# MiniDuino.net
KiCad netlist of a schematic drawn in EAGLE
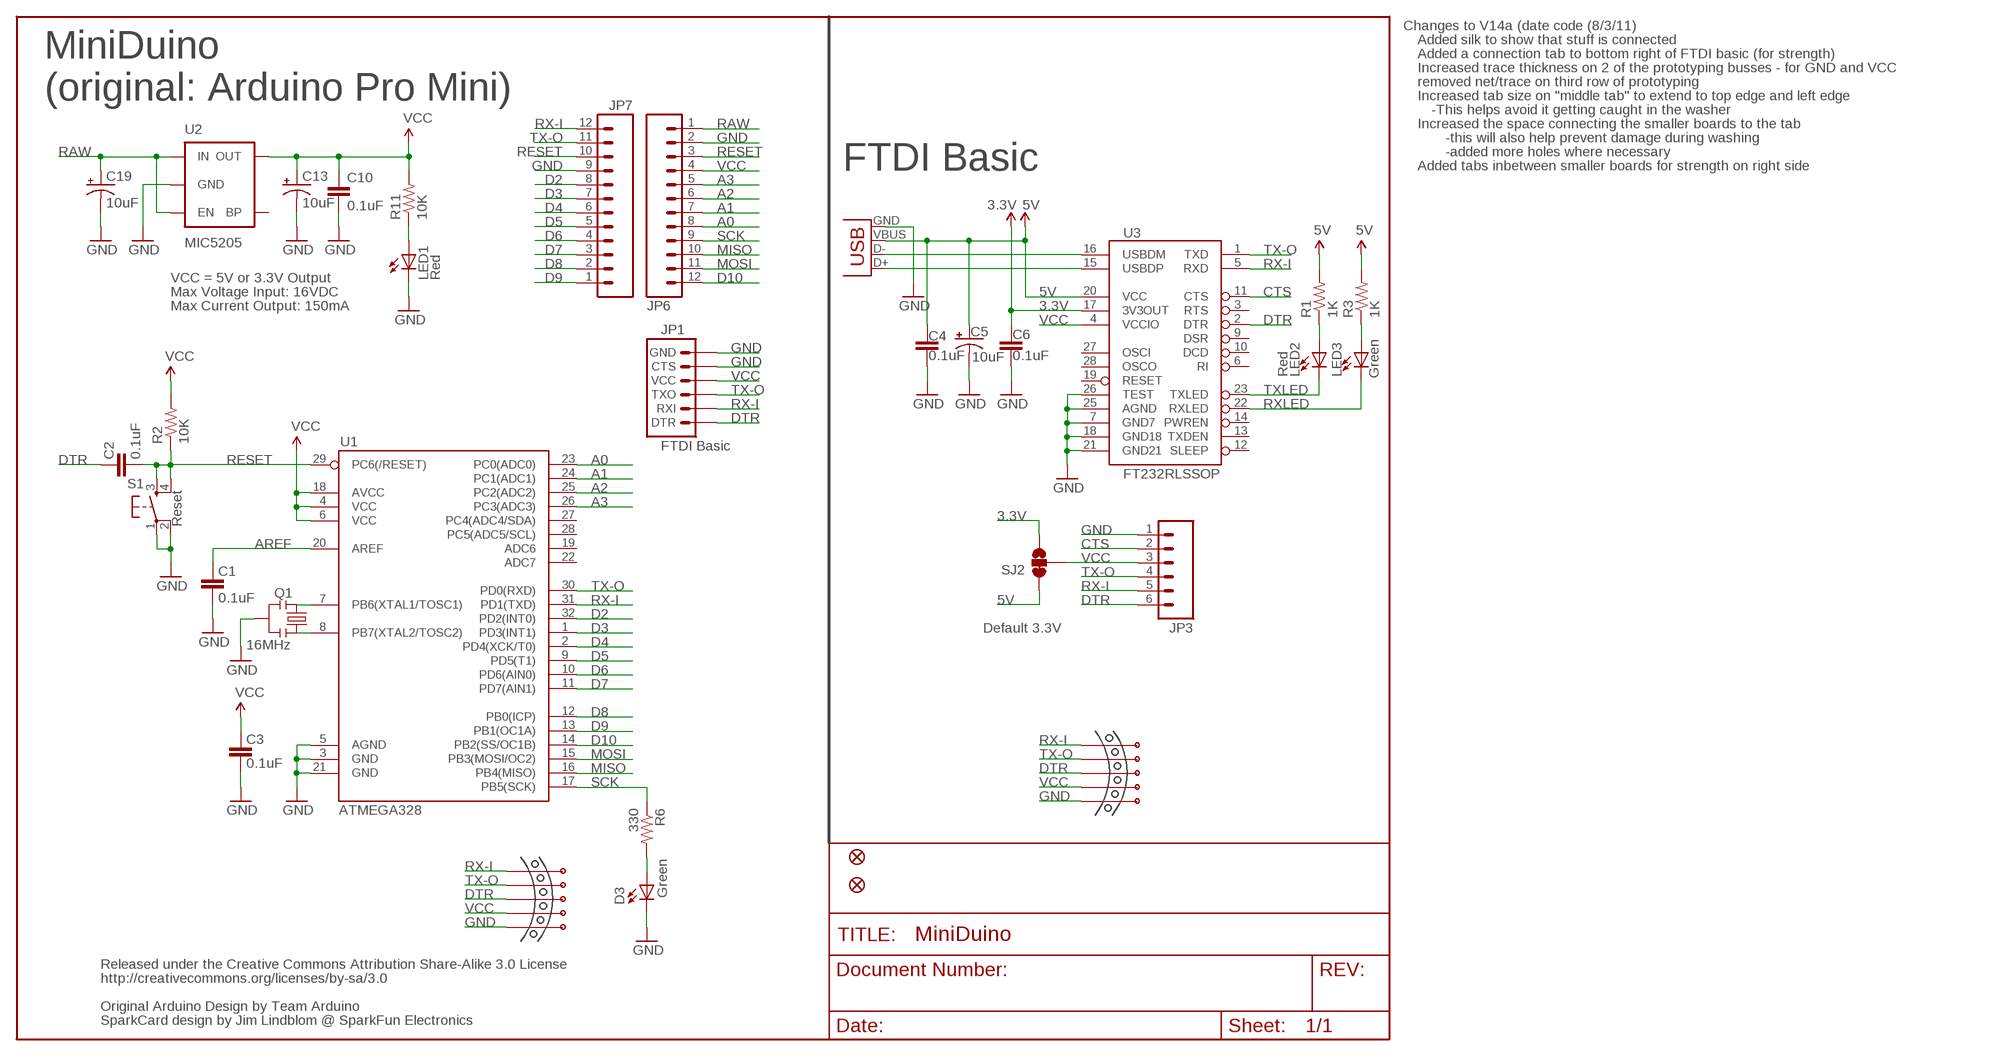
[diagram p0: schematic, sheet 1]

(export (version "E")
  (design (tool "Eeschema 10.0.6"))
  (components
    (comp (ref "C1")
      (value "0.1uF")
      (footprint "eagle-import:0402-CAP")
      (libsource (lib "eagle-import") (part "CAP0402-CAP"))
    )
    (comp (ref "C2")
      (value "0.1uF")
      (footprint "eagle-import:0402-CAP")
      (libsource (lib "eagle-import") (part "CAP0402-CAP"))
    )
    (comp (ref "C3")
      (value "0.1uF")
      (footprint "eagle-import:0402-CAP")
      (libsource (lib "eagle-import") (part "CAP0402-CAP"))
    )
    (comp (ref "C4")
      (value "0.1uF")
      (footprint "eagle-import:0402-CAP")
      (libsource (lib "eagle-import") (part "CAP0402-CAP"))
    )
    (comp (ref "C5")
      (value "10uF")
      (footprint "eagle-import:EIA3216")
      (libsource (lib "eagle-import") (part "CAP_POL1206"))
    )
    (comp (ref "C6")
      (value "0.1uF")
      (footprint "eagle-import:0402-CAP")
      (libsource (lib "eagle-import") (part "CAP0402-CAP"))
    )
    (comp (ref "C10")
      (value "0.1uF")
      (footprint "eagle-import:0402-CAP")
      (libsource (lib "eagle-import") (part "CAP0402-CAP"))
    )
    (comp (ref "C13")
      (value "10uF")
      (footprint "eagle-import:EIA3216")
      (libsource (lib "eagle-import") (part "CAP_POL1206"))
    )
    (comp (ref "C19")
      (value "10uF")
      (footprint "eagle-import:EIA3216")
      (libsource (lib "eagle-import") (part "CAP_POL1206"))
    )
    (comp (ref "D3")
      (value "Green")
      (footprint "eagle-import:LED-0603")
      (libsource (lib "eagle-import") (part "LED0603"))
    )
    (comp (ref "JP1")
      (value "FTDI Basic")
      (footprint "eagle-import:1X06")
      (libsource (lib "eagle-import") (part "ARDUINO_SERIAL_PROGRAMPTH"))
    )
    (comp (ref "JP3")
      (value "M06SIP")
      (footprint "eagle-import:1X06")
      (libsource (lib "eagle-import") (part "M06SIP"))
    )
    (comp (ref "JP6")
      (value "M12PTH")
      (footprint "eagle-import:1X12")
      (libsource (lib "eagle-import") (part "M12PTH"))
    )
    (comp (ref "JP7")
      (value "M12PTH")
      (footprint "eagle-import:1X12")
      (libsource (lib "eagle-import") (part "M12PTH"))
    )
    (comp (ref "JP16")
      (value "FIDUCIAL1X2.5")
      (footprint "eagle-import:FIDUCIAL-1X2.5")
      (libsource (lib "eagle-import") (part "FIDUCIAL1X2.5"))
    )
    (comp (ref "JP19")
      (value "FIDUCIAL1X2.5")
      (footprint "eagle-import:FIDUCIAL-1X2.5")
      (libsource (lib "eagle-import") (part "FIDUCIAL1X2.5"))
    )
    (comp (ref "LED1")
      (value "Red")
      (footprint "eagle-import:LED-0603")
      (libsource (lib "eagle-import") (part "LED0603"))
    )
    (comp (ref "LED2")
      (value "Red")
      (footprint "eagle-import:LED-0603")
      (libsource (lib "eagle-import") (part "LED0603"))
    )
    (comp (ref "LED3")
      (value "Green")
      (footprint "eagle-import:LED-0603")
      (libsource (lib "eagle-import") (part "LED0603"))
    )
    (comp (ref "Q1")
      (value "16MHz")
      (footprint "eagle-import:RESONATOR-SMD")
      (libsource (lib "eagle-import") (part "RESONATORSMD"))
    )
    (comp (ref "R1")
      (value "1K")
      (footprint "eagle-import:0402-RES")
      (libsource (lib "eagle-import") (part "RESISTOR0402-RES"))
    )
    (comp (ref "R2")
      (value "10K")
      (footprint "eagle-import:0402-RES")
      (libsource (lib "eagle-import") (part "RESISTOR0402-RES"))
    )
    (comp (ref "R3")
      (value "1K")
      (footprint "eagle-import:0402-RES")
      (libsource (lib "eagle-import") (part "RESISTOR0402-RES"))
    )
    (comp (ref "R6")
      (value "330")
      (footprint "eagle-import:0402-RES")
      (libsource (lib "eagle-import") (part "RESISTOR0402-RES"))
    )
    (comp (ref "R11")
      (value "10K")
      (footprint "eagle-import:0402-RES")
      (libsource (lib "eagle-import") (part "RESISTOR0402-RES"))
    )
    (comp (ref "S1")
      (value "Reset")
      (footprint "eagle-import:TACTILE_SWITCH_SMD")
      (libsource (lib "eagle-import") (part "TAC_SWITCHSMD"))
    )
    (comp (ref "SJ2")
      (value "SOLDERJUMPER_2WAYS")
      (footprint "eagle-import:SJ_3")
      (libsource (lib "eagle-import") (part "SOLDERJUMPER_2WAYS"))
    )
    (comp (ref "U$22")
      (value "MOUSE-BITE-5")
      (footprint "eagle-import:MOUSE-BITE-5")
      (libsource (lib "eagle-import") (part "MOUSE-BITE-5"))
    )
    (comp (ref "U$23")
      (value "MOUSE-BITE-5")
      (footprint "eagle-import:MOUSE-BITE-5")
      (libsource (lib "eagle-import") (part "MOUSE-BITE-5"))
    )
    (comp (ref "U1")
      (value "ATMEGA328")
      (footprint "eagle-import:TQFP32-08")
      (libsource (lib "eagle-import") (part "ATMEGA168"))
    )
    (comp (ref "U2")
      (value "MIC5205")
      (footprint "eagle-import:SOT23-5")
      (libsource (lib "eagle-import") (part "V_REG_LDOSMD"))
    )
    (comp (ref "U3")
      (value "FT232RLSSOP")
      (footprint "eagle-import:SSOP28DB")
      (libsource (lib "eagle-import") (part "FT232RLSSOP"))
    )
    (comp (ref "X2")
      (value "USB-SMD-NS")
      (footprint "eagle-import:USB-MINIB-NOSTOP")
      (libsource (lib "eagle-import") (part "USB-SMD-NS"))
    )
  )
  (nets
    (net (code "1") (name "/A0") (class "Default")
      (node (ref "JP6") (pin "8") (pinfunction "8_8") (pintype "passive"))
      (node (ref "U1") (pin "23") (pinfunction "PC0(ADC0)_23") (pintype "bidirectional"))
    )
    (net (code "2") (name "/A1") (class "Default")
      (node (ref "JP6") (pin "7") (pinfunction "7_7") (pintype "passive"))
      (node (ref "U1") (pin "24") (pinfunction "PC1(ADC1)_24") (pintype "bidirectional"))
    )
    (net (code "3") (name "/A2") (class "Default")
      (node (ref "JP6") (pin "6") (pinfunction "6_6") (pintype "passive"))
      (node (ref "U1") (pin "25") (pinfunction "PC2(ADC2)_25") (pintype "bidirectional"))
    )
    (net (code "4") (name "/A3") (class "Default")
      (node (ref "JP6") (pin "5") (pinfunction "5_5") (pintype "passive"))
      (node (ref "U1") (pin "26") (pinfunction "PC3(ADC3)_26") (pintype "bidirectional"))
    )
    (net (code "5") (name "/AREF") (class "Default")
      (node (ref "C1") (pin "2") (pinfunction "2_2") (pintype "passive"))
      (node (ref "U1") (pin "20") (pinfunction "AREF_20") (pintype "bidirectional"))
    )
    (net (code "6") (name "/CTS") (class "Default")
      (node (ref "JP3") (pin "2") (pinfunction "2_2") (pintype "passive"))
      (node (ref "U3") (pin "11") (pinfunction "CTS_11") (pintype "input"))
    )
    (net (code "7") (name "/D2") (class "Default")
      (node (ref "JP7") (pin "8") (pinfunction "8_8") (pintype "passive"))
      (node (ref "U1") (pin "32") (pinfunction "PD2(INT0)_32") (pintype "bidirectional"))
    )
    (net (code "8") (name "/D3") (class "Default")
      (node (ref "JP7") (pin "7") (pinfunction "7_7") (pintype "passive"))
      (node (ref "U1") (pin "1") (pinfunction "PD3(INT1)_1") (pintype "bidirectional"))
    )
    (net (code "9") (name "/D4") (class "Default")
      (node (ref "JP7") (pin "6") (pinfunction "6_6") (pintype "passive"))
      (node (ref "U1") (pin "2") (pinfunction "PD4(XCK/T0)_2") (pintype "bidirectional"))
    )
    (net (code "10") (name "/D5") (class "Default")
      (node (ref "JP7") (pin "5") (pinfunction "5_5") (pintype "passive"))
      (node (ref "U1") (pin "9") (pinfunction "PD5(T1)_9") (pintype "bidirectional"))
    )
    (net (code "11") (name "/D6") (class "Default")
      (node (ref "JP7") (pin "4") (pinfunction "4_4") (pintype "passive"))
      (node (ref "U1") (pin "10") (pinfunction "PD6(AIN0)_10") (pintype "bidirectional"))
    )
    (net (code "12") (name "/D7") (class "Default")
      (node (ref "JP7") (pin "3") (pinfunction "3_3") (pintype "passive"))
      (node (ref "U1") (pin "11") (pinfunction "PD7(AIN1)_11") (pintype "bidirectional"))
    )
    (net (code "13") (name "/D8") (class "Default")
      (node (ref "JP7") (pin "2") (pinfunction "2_2") (pintype "passive"))
      (node (ref "U1") (pin "12") (pinfunction "PB0(ICP)_12") (pintype "bidirectional"))
    )
    (net (code "14") (name "/D9") (class "Default")
      (node (ref "JP7") (pin "1") (pinfunction "1_1") (pintype "passive"))
      (node (ref "U1") (pin "13") (pinfunction "PB1(OC1A)_13") (pintype "bidirectional"))
    )
    (net (code "15") (name "/D10") (class "Default")
      (node (ref "JP6") (pin "12") (pinfunction "12_12") (pintype "passive"))
      (node (ref "U1") (pin "14") (pinfunction "PB2(SS/OC1B)_14") (pintype "bidirectional"))
    )
    (net (code "16") (name "/DTR") (class "Default")
      (node (ref "C2") (pin "2") (pinfunction "2_2") (pintype "passive"))
      (node (ref "JP1") (pin "1") (pinfunction "DTR_1") (pintype "passive"))
      (node (ref "JP3") (pin "6") (pinfunction "6_6") (pintype "passive"))
      (node (ref "U$22") (pin "P$3") (pinfunction "P$3_P$3") (pintype "bidirectional"))
      (node (ref "U$23") (pin "P$3") (pinfunction "P$3_P$3") (pintype "bidirectional"))
      (node (ref "U3") (pin "2") (pinfunction "DTR_2") (pintype "output"))
    )
    (net (code "17") (name "/MISO") (class "Default")
      (node (ref "JP6") (pin "10") (pinfunction "10_10") (pintype "passive"))
      (node (ref "U1") (pin "16") (pinfunction "PB4(MISO)_16") (pintype "bidirectional"))
    )
    (net (code "18") (name "/MOSI") (class "Default")
      (node (ref "JP6") (pin "11") (pinfunction "11_11") (pintype "passive"))
      (node (ref "U1") (pin "15") (pinfunction "PB3(MOSI/OC2)_15") (pintype "bidirectional"))
    )
    (net (code "19") (name "/RAW") (class "Default")
      (node (ref "C19") (pin "A") (pinfunction "+_A") (pintype "passive"))
      (node (ref "JP6") (pin "1") (pinfunction "1_1") (pintype "passive"))
      (node (ref "U2") (pin "1") (pinfunction "IN_1") (pintype "input"))
      (node (ref "U2") (pin "3") (pinfunction "EN_3") (pintype "input"))
    )
    (net (code "20") (name "/RESET") (class "Default")
      (node (ref "C2") (pin "1") (pinfunction "1_1") (pintype "passive"))
      (node (ref "JP6") (pin "3") (pinfunction "3_3") (pintype "passive"))
      (node (ref "JP7") (pin "10") (pinfunction "10_10") (pintype "passive"))
      (node (ref "R2") (pin "1") (pinfunction "1_1") (pintype "passive"))
      (node (ref "S1") (pin "3") (pinfunction "3_3") (pintype "passive"))
      (node (ref "S1") (pin "4") (pinfunction "4_4") (pintype "passive"))
      (node (ref "U1") (pin "29") (pinfunction "PC6(/RESET)_29") (pintype "bidirectional"))
    )
    (net (code "21") (name "/RX-I") (class "Default")
      (node (ref "JP1") (pin "2") (pinfunction "RXI_2") (pintype "passive"))
      (node (ref "JP3") (pin "5") (pinfunction "5_5") (pintype "passive"))
      (node (ref "JP7") (pin "12") (pinfunction "12_12") (pintype "passive"))
      (node (ref "U$22") (pin "P$1") (pinfunction "P$1_P$1") (pintype "bidirectional"))
      (node (ref "U$23") (pin "P$1") (pinfunction "P$1_P$1") (pintype "bidirectional"))
      (node (ref "U1") (pin "31") (pinfunction "PD1(TXD)_31") (pintype "bidirectional"))
      (node (ref "U3") (pin "5") (pinfunction "RXD_5") (pintype "input"))
    )
    (net (code "22") (name "/RXLED") (class "Default")
      (node (ref "LED3") (pin "C") (pinfunction "C_C") (pintype "passive"))
      (node (ref "U3") (pin "22") (pinfunction "RXLED_22") (pintype "input"))
    )
    (net (code "23") (name "/SCK") (class "Default")
      (node (ref "JP6") (pin "9") (pinfunction "9_9") (pintype "passive"))
      (node (ref "R6") (pin "1") (pinfunction "1_1") (pintype "passive"))
      (node (ref "U1") (pin "17") (pinfunction "PB5(SCK)_17") (pintype "bidirectional"))
    )
    (net (code "24") (name "/TX-O") (class "Default")
      (node (ref "JP1") (pin "3") (pinfunction "TXO_3") (pintype "passive"))
      (node (ref "JP3") (pin "4") (pinfunction "4_4") (pintype "passive"))
      (node (ref "JP7") (pin "11") (pinfunction "11_11") (pintype "passive"))
      (node (ref "U$22") (pin "P$2") (pinfunction "P$2_P$2") (pintype "bidirectional"))
      (node (ref "U$23") (pin "P$2") (pinfunction "P$2_P$2") (pintype "bidirectional"))
      (node (ref "U1") (pin "30") (pinfunction "PD0(RXD)_30") (pintype "bidirectional"))
      (node (ref "U3") (pin "1") (pinfunction "TXD_1") (pintype "output"))
    )
    (net (code "25") (name "/TXLED") (class "Default")
      (node (ref "LED2") (pin "C") (pinfunction "C_C") (pintype "passive"))
      (node (ref "U3") (pin "23") (pinfunction "TXLED_23") (pintype "input"))
    )
    (net (code "26") (name "3.3V") (class "Default")
      (node (ref "C6") (pin "1") (pinfunction "1_1") (pintype "passive"))
      (node (ref "SJ2") (pin "3") (pinfunction "3_3") (pintype "passive"))
      (node (ref "U3") (pin "17") (pinfunction "3V3OUT_17") (pintype "output"))
    )
    (net (code "27") (name "5V") (class "Default")
      (node (ref "C4") (pin "1") (pinfunction "1_1") (pintype "passive"))
      (node (ref "C5") (pin "A") (pinfunction "+_A") (pintype "passive"))
      (node (ref "R1") (pin "2") (pinfunction "2_2") (pintype "passive"))
      (node (ref "R3") (pin "2") (pinfunction "2_2") (pintype "passive"))
      (node (ref "SJ2") (pin "1") (pinfunction "1_1") (pintype "passive"))
      (node (ref "U3") (pin "20") (pinfunction "VCC_20") (pintype "power_in"))
      (node (ref "X2") (pin "VBUS") (pinfunction "VBUS_VBUS") (pintype "bidirectional"))
    )
    (net (code "28") (name "GND") (class "Default")
      (node (ref "C1") (pin "1") (pinfunction "1_1") (pintype "passive"))
      (node (ref "C10") (pin "2") (pinfunction "2_2") (pintype "passive"))
      (node (ref "C13") (pin "C") (pinfunction "-_C") (pintype "passive"))
      (node (ref "C19") (pin "C") (pinfunction "-_C") (pintype "passive"))
      (node (ref "C3") (pin "1") (pinfunction "1_1") (pintype "passive"))
      (node (ref "C4") (pin "2") (pinfunction "2_2") (pintype "passive"))
      (node (ref "C5") (pin "C") (pinfunction "-_C") (pintype "passive"))
      (node (ref "C6") (pin "2") (pinfunction "2_2") (pintype "passive"))
      (node (ref "D3") (pin "C") (pinfunction "C_C") (pintype "passive"))
      (node (ref "JP1") (pin "5") (pinfunction "CTS_5") (pintype "passive"))
      (node (ref "JP1") (pin "6") (pinfunction "GND_6") (pintype "passive"))
      (node (ref "JP3") (pin "1") (pinfunction "1_1") (pintype "passive"))
      (node (ref "JP6") (pin "2") (pinfunction "2_2") (pintype "passive"))
      (node (ref "JP7") (pin "9") (pinfunction "9_9") (pintype "passive"))
      (node (ref "LED1") (pin "C") (pinfunction "C_C") (pintype "passive"))
      (node (ref "Q1") (pin "2") (pinfunction "2_2") (pintype "passive"))
      (node (ref "S1") (pin "1") (pinfunction "1_1") (pintype "passive"))
      (node (ref "S1") (pin "2") (pinfunction "2_2") (pintype "passive"))
      (node (ref "U$22") (pin "P$5") (pinfunction "P$5_P$5") (pintype "bidirectional"))
      (node (ref "U$23") (pin "P$5") (pinfunction "P$5_P$5") (pintype "bidirectional"))
      (node (ref "U1") (pin "21") (pinfunction "GND_21") (pintype "bidirectional"))
      (node (ref "U1") (pin "3") (pinfunction "GND_3") (pintype "bidirectional"))
      (node (ref "U1") (pin "5") (pinfunction "AGND_5") (pintype "bidirectional"))
      (node (ref "U2") (pin "2") (pinfunction "GND_2") (pintype "input"))
      (node (ref "U3") (pin "18") (pinfunction "GND18_18") (pintype "power_in"))
      (node (ref "U3") (pin "21") (pinfunction "GND21_21") (pintype "power_in"))
      (node (ref "U3") (pin "25") (pinfunction "AGND_25") (pintype "power_in"))
      (node (ref "U3") (pin "26") (pinfunction "TEST_26") (pintype "input"))
      (node (ref "U3") (pin "7") (pinfunction "GND7_7") (pintype "power_in"))
      (node (ref "X2") (pin "GND") (pinfunction "GND_GND") (pintype "bidirectional"))
    )
    (net (code "29") (name "Net-(D3-PadA)") (class "Default")
      (node (ref "D3") (pin "A") (pinfunction "A_A") (pintype "passive"))
      (node (ref "R6") (pin "2") (pinfunction "2_2") (pintype "passive"))
    )
    (net (code "30") (name "Net-(LED1-PadA)") (class "Default")
      (node (ref "LED1") (pin "A") (pinfunction "A_A") (pintype "passive"))
      (node (ref "R11") (pin "1") (pinfunction "1_1") (pintype "passive"))
    )
    (net (code "31") (name "Net-(LED2-PadA)") (class "Default")
      (node (ref "LED2") (pin "A") (pinfunction "A_A") (pintype "passive"))
      (node (ref "R1") (pin "1") (pinfunction "1_1") (pintype "passive"))
    )
    (net (code "32") (name "Net-(LED3-PadA)") (class "Default")
      (node (ref "LED3") (pin "A") (pinfunction "A_A") (pintype "passive"))
      (node (ref "R3") (pin "1") (pinfunction "1_1") (pintype "passive"))
    )
    (net (code "33") (name "Net-(U1-PB6(XTAL1{slash}TOSC1))") (class "Default")
      (node (ref "Q1") (pin "3") (pinfunction "3_3") (pintype "passive"))
      (node (ref "U1") (pin "7") (pinfunction "PB6(XTAL1/TOSC1)_7") (pintype "bidirectional"))
    )
    (net (code "34") (name "Net-(U1-PB7(XTAL2{slash}TOSC2))") (class "Default")
      (node (ref "Q1") (pin "1") (pinfunction "1_1") (pintype "passive"))
      (node (ref "U1") (pin "8") (pinfunction "PB7(XTAL2/TOSC2)_8") (pintype "bidirectional"))
    )
    (net (code "35") (name "Net-(U3-USBDM)") (class "Default")
      (node (ref "U3") (pin "16") (pinfunction "USBDM_16") (pintype "bidirectional"))
      (node (ref "X2") (pin "D-") (pinfunction "D-_D-") (pintype "bidirectional"))
    )
    (net (code "36") (name "Net-(U3-USBDP)") (class "Default")
      (node (ref "U3") (pin "15") (pinfunction "USBDP_15") (pintype "bidirectional"))
      (node (ref "X2") (pin "D+") (pinfunction "D+_D+") (pintype "bidirectional"))
    )
    (net (code "37") (name "VCC") (class "Default")
      (node (ref "C10") (pin "1") (pinfunction "1_1") (pintype "passive"))
      (node (ref "C13") (pin "A") (pinfunction "+_A") (pintype "passive"))
      (node (ref "C3") (pin "2") (pinfunction "2_2") (pintype "passive"))
      (node (ref "JP1") (pin "4") (pinfunction "VCC_4") (pintype "passive"))
      (node (ref "JP3") (pin "3") (pinfunction "3_3") (pintype "passive"))
      (node (ref "JP6") (pin "4") (pinfunction "4_4") (pintype "passive"))
      (node (ref "R11") (pin "2") (pinfunction "2_2") (pintype "passive"))
      (node (ref "R2") (pin "2") (pinfunction "2_2") (pintype "passive"))
      (node (ref "SJ2") (pin "2") (pinfunction "2_2") (pintype "passive"))
      (node (ref "U$22") (pin "P$4") (pinfunction "P$4_P$4") (pintype "bidirectional"))
      (node (ref "U$23") (pin "P$4") (pinfunction "P$4_P$4") (pintype "bidirectional"))
      (node (ref "U1") (pin "18") (pinfunction "AVCC_18") (pintype "bidirectional"))
      (node (ref "U1") (pin "4") (pinfunction "VCC_4") (pintype "bidirectional"))
      (node (ref "U1") (pin "6") (pinfunction "VCC_6") (pintype "bidirectional"))
      (node (ref "U2") (pin "5") (pinfunction "OUT_5") (pintype "passive"))
      (node (ref "U3") (pin "4") (pinfunction "VCCIO_4") (pintype "power_in"))
    )
    (net (code "38") (name "unconnected-(U1-ADC6-Pad19)") (class "Default")
      (node (ref "U1") (pin "19") (pinfunction "ADC6_19") (pintype "bidirectional"))
    )
    (net (code "39") (name "unconnected-(U1-ADC7-Pad22)") (class "Default")
      (node (ref "U1") (pin "22") (pinfunction "ADC7_22") (pintype "bidirectional"))
    )
    (net (code "40") (name "unconnected-(U1-PC4(ADC4{slash}SDA)-Pad27)") (class "Default")
      (node (ref "U1") (pin "27") (pinfunction "PC4(ADC4/SDA)_27") (pintype "bidirectional"))
    )
    (net (code "41") (name "unconnected-(U1-PC5(ADC5{slash}SCL)-Pad28)") (class "Default")
      (node (ref "U1") (pin "28") (pinfunction "PC5(ADC5/SCL)_28") (pintype "bidirectional"))
    )
    (net (code "42") (name "unconnected-(U2-BP-Pad4)") (class "Default")
      (node (ref "U2") (pin "4") (pinfunction "BP_4") (pintype "input"))
    )
    (net (code "43") (name "unconnected-(U3-DCD-Pad10)") (class "Default")
      (node (ref "U3") (pin "10") (pinfunction "DCD_10") (pintype "input"))
    )
    (net (code "44") (name "unconnected-(U3-DSR-Pad9)") (class "Default")
      (node (ref "U3") (pin "9") (pinfunction "DSR_9") (pintype "input"))
    )
    (net (code "45") (name "unconnected-(U3-OSCI-Pad27)") (class "Default")
      (node (ref "U3") (pin "27") (pinfunction "OSCI_27") (pintype "input"))
    )
    (net (code "46") (name "unconnected-(U3-OSCO-Pad28)") (class "Default")
      (node (ref "U3") (pin "28") (pinfunction "OSCO_28") (pintype "output"))
    )
    (net (code "47") (name "unconnected-(U3-PWREN-Pad14)") (class "Default")
      (node (ref "U3") (pin "14") (pinfunction "PWREN_14") (pintype "input"))
    )
    (net (code "48") (name "unconnected-(U3-RESET-Pad19)") (class "Default")
      (node (ref "U3") (pin "19") (pinfunction "RESET_19") (pintype "input"))
    )
    (net (code "49") (name "unconnected-(U3-RI-Pad6)") (class "Default")
      (node (ref "U3") (pin "6") (pinfunction "RI_6") (pintype "input"))
    )
    (net (code "50") (name "unconnected-(U3-RTS-Pad3)") (class "Default")
      (node (ref "U3") (pin "3") (pinfunction "RTS_3") (pintype "output"))
    )
    (net (code "51") (name "unconnected-(U3-SLEEP-Pad12)") (class "Default")
      (node (ref "U3") (pin "12") (pinfunction "SLEEP_12") (pintype "input"))
    )
    (net (code "52") (name "unconnected-(U3-TXDEN-Pad13)") (class "Default")
      (node (ref "U3") (pin "13") (pinfunction "TXDEN_13") (pintype "input"))
    )
  )
)
